# RS232.net
KiCad netlist of a schematic drawn in Altium Designer
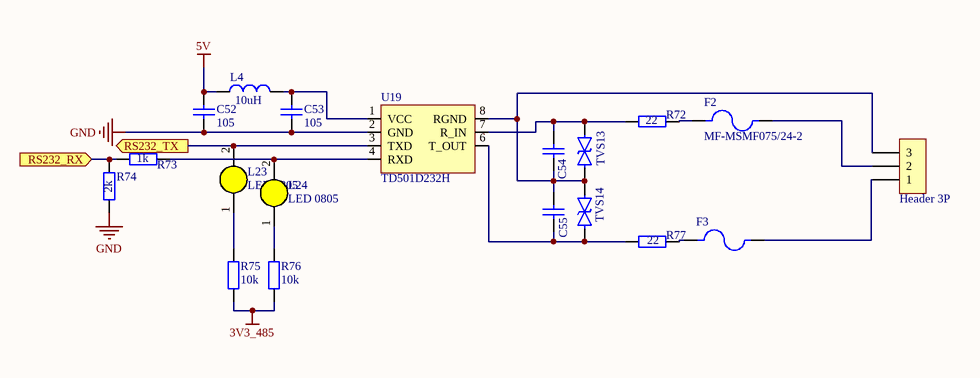
[diagram p0: RS232.SchDoc]

(export (version "E")
  (design (tool "Eeschema 10.0.6"))
  (components
    (comp (ref "C52") (value "105") (footprint "0603_Cap") (libsource (lib "CMN") (part "Ceramic Capacitor")))
    (comp (ref "C53") (value "105") (footprint "0603_Cap") (libsource (lib "CMN") (part "Ceramic Capacitor")))
    (comp (ref "C54") (value "101") (footprint "0603_Cap") (libsource (lib "CMN") (part "Ceramic Capacitor")))
    (comp (ref "C55") (value "101") (footprint "0603_Cap") (libsource (lib "CMN") (part "Ceramic Capacitor")))
    (comp (ref "F2")
      (value "MF-MSMF075/24-2")
      (footprint "FUSER_MF-MSMF075/24-2")
      (description "Polymeric PTC Resettable Fuse 24V 750 mA Ih Surface Mount 1812 (4532 Metric), Concave")
      (fields (field (name "MF") "Bourns"))
      (libsource (lib "MF-MSMF075_24-2") (part "MF-MSMF075/24-2"))
    )
    (comp (ref "F3")
      (value "MF-MSMF075/24-2")
      (footprint "FUSER_MF-MSMF075/24-2")
      (description "Polymeric PTC Resettable Fuse 24V 750 mA Ih Surface Mount 1812 (4532 Metric), Concave")
      (fields (field (name "MF") "Bourns"))
      (libsource (lib "MF-MSMF075_24-2") (part "MF-MSMF075/24-2"))
    )
    (comp (ref "H23")
      (value "Header 3P")
      (footprint "CON 3 EDG5.08-3P")
      (description "THT")
      (libsource (lib "CMN") (part "Header 3P"))
    )
    (comp (ref "L4")
      (value "10uH")
      (footprint "0603_Inductor")
      (fields (field (name "MP") "B82477G4472M000") (field (name "MF") "EPCOS"))
      (libsource (lib "CMN") (part "Inductor"))
    )
    (comp (ref "L23")
      (value "LED 0805")
      (footprint "LED-0805-Yellow")
      (description "Dán")
      (libsource (lib "Led") (part "LED 0805 Vang"))
    )
    (comp (ref "L24")
      (value "LED 0805")
      (footprint "LED-0805-Yellow")
      (description "Dán")
      (libsource (lib "Led") (part "LED 0805 Vang"))
    )
    (comp (ref "R72") (value "22") (footprint "0603_Res") (libsource (lib "CMN") (part "Resistor")))
    (comp (ref "R73") (value "1k") (footprint "0603_Res") (libsource (lib "CMN") (part "Resistor")))
    (comp (ref "R74") (value "2k") (footprint "0603_Res") (libsource (lib "CMN") (part "Resistor")))
    (comp (ref "R75") (value "10k") (footprint "0603_Res") (libsource (lib "CMN") (part "Resistor")))
    (comp (ref "R76") (value "10k") (footprint "0603_Res") (libsource (lib "CMN") (part "Resistor")))
    (comp (ref "R77") (value "22") (footprint "0603_Res") (libsource (lib "CMN") (part "Resistor")))
    (comp (ref "TVS13")
      (value "SMBJ12CA")
      (footprint "SMB - DO-214AA")
      (libsource (lib "CMN") (part "TVS Bi Diode"))
    )
    (comp (ref "TVS14")
      (value "SMBJ12CA")
      (footprint "SMB - DO-214AA")
      (libsource (lib "CMN") (part "TVS Bi Diode"))
    )
    (comp (ref "U19")
      (value "TD501D232H")
      (footprint "TD501D232H")
      (libsource (lib "CMN") (part "TD501D232H"))
    )
  )
  (nets
    (net (code "1") (name "/RS232_RX") (class "Default")
      (node (ref "R73") (pin "1") (pinfunction "1_1") (pintype "passive"))
      (node (ref "R74") (pin "2") (pinfunction "2_2") (pintype "passive"))
    )
    (net (code "2") (name "/RS232_TX") (class "Default")
      (node (ref "L23") (pin "2") (pinfunction "K_2") (pintype "passive"))
      (node (ref "U19") (pin "3") (pinfunction "TXD_3") (pintype "passive"))
    )
    (net (code "3") (name "3V3_485") (class "Default")
      (node (ref "R75") (pin "2") (pinfunction "2_2") (pintype "passive"))
      (node (ref "R76") (pin "2") (pinfunction "2_2") (pintype "passive"))
    )
    (net (code "4") (name "5V") (class "Default")
      (node (ref "C52") (pin "1") (pinfunction "1_1") (pintype "passive"))
      (node (ref "L4") (pin "1") (pinfunction "1_1") (pintype "passive"))
    )
    (net (code "5") (name "GND") (class "Default")
      (node (ref "C52") (pin "2") (pinfunction "2_2") (pintype "passive"))
      (node (ref "C53") (pin "2") (pinfunction "2_2") (pintype "passive"))
      (node (ref "R74") (pin "1") (pinfunction "1_1") (pintype "passive"))
      (node (ref "U19") (pin "2") (pinfunction "GND_2") (pintype "passive"))
    )
    (net (code "6") (name "Net-(F2-Pad1)") (class "Default")
      (node (ref "F2") (pin "1") (pinfunction "1_1") (pintype "passive"))
      (node (ref "R72") (pin "1") (pinfunction "1_1") (pintype "passive"))
    )
    (net (code "7") (name "Net-(F2-Pad2)") (class "Default")
      (node (ref "F2") (pin "2") (pinfunction "2_2") (pintype "passive"))
      (node (ref "H23") (pin "2") (pinfunction "2_2") (pintype "passive"))
    )
    (net (code "8") (name "Net-(F3-Pad1)") (class "Default")
      (node (ref "F3") (pin "1") (pinfunction "1_1") (pintype "passive"))
      (node (ref "R77") (pin "1") (pinfunction "1_1") (pintype "passive"))
    )
    (net (code "9") (name "Net-(F3-Pad2)") (class "Default")
      (node (ref "F3") (pin "2") (pinfunction "2_2") (pintype "passive"))
      (node (ref "H23") (pin "1") (pinfunction "1_1") (pintype "passive"))
    )
    (net (code "10") (name "Net-(L23-A)") (class "Default")
      (node (ref "L23") (pin "1") (pinfunction "A_1") (pintype "passive"))
      (node (ref "R75") (pin "1") (pinfunction "1_1") (pintype "passive"))
    )
    (net (code "11") (name "Net-(L24-A)") (class "Default")
      (node (ref "L24") (pin "1") (pinfunction "A_1") (pintype "passive"))
      (node (ref "R76") (pin "1") (pinfunction "1_1") (pintype "passive"))
    )
    (net (code "12") (name "Net-(L24-K)") (class "Default")
      (node (ref "L24") (pin "2") (pinfunction "K_2") (pintype "passive"))
      (node (ref "R73") (pin "2") (pinfunction "2_2") (pintype "passive"))
      (node (ref "U19") (pin "4") (pinfunction "RXD_4") (pintype "passive"))
    )
    (net (code "13") (name "Net-(U19-RGND)") (class "Default")
      (node (ref "C54") (pin "2") (pinfunction "2_2") (pintype "passive"))
      (node (ref "C55") (pin "1") (pinfunction "1_1") (pintype "passive"))
      (node (ref "H23") (pin "3") (pinfunction "3_3") (pintype "passive"))
      (node (ref "TVS13") (pin "1") (pinfunction "1_1") (pintype "passive"))
      (node (ref "TVS14") (pin "2") (pinfunction "2_2") (pintype "passive"))
      (node (ref "U19") (pin "8") (pinfunction "RGND_8") (pintype "passive"))
    )
    (net (code "14") (name "Net-(U19-R_IN)") (class "Default")
      (node (ref "C54") (pin "1") (pinfunction "1_1") (pintype "passive"))
      (node (ref "R72") (pin "2") (pinfunction "2_2") (pintype "passive"))
      (node (ref "TVS13") (pin "2") (pinfunction "2_2") (pintype "passive"))
      (node (ref "U19") (pin "7") (pinfunction "R_IN_7") (pintype "passive"))
    )
    (net (code "15") (name "Net-(U19-T_OUT)") (class "Default")
      (node (ref "C55") (pin "2") (pinfunction "2_2") (pintype "passive"))
      (node (ref "R77") (pin "2") (pinfunction "2_2") (pintype "passive"))
      (node (ref "TVS14") (pin "1") (pinfunction "1_1") (pintype "passive"))
      (node (ref "U19") (pin "6") (pinfunction "T_OUT_6") (pintype "passive"))
    )
    (net (code "16") (name "Net-(U19-VCC)") (class "Default")
      (node (ref "C53") (pin "1") (pinfunction "1_1") (pintype "passive"))
      (node (ref "L4") (pin "2") (pinfunction "2_2") (pintype "passive"))
      (node (ref "U19") (pin "1") (pinfunction "VCC_1") (pintype "passive"))
    )
  )
)
